# rtc.net
KiCad netlist of a schematic drawn in Altium Designer
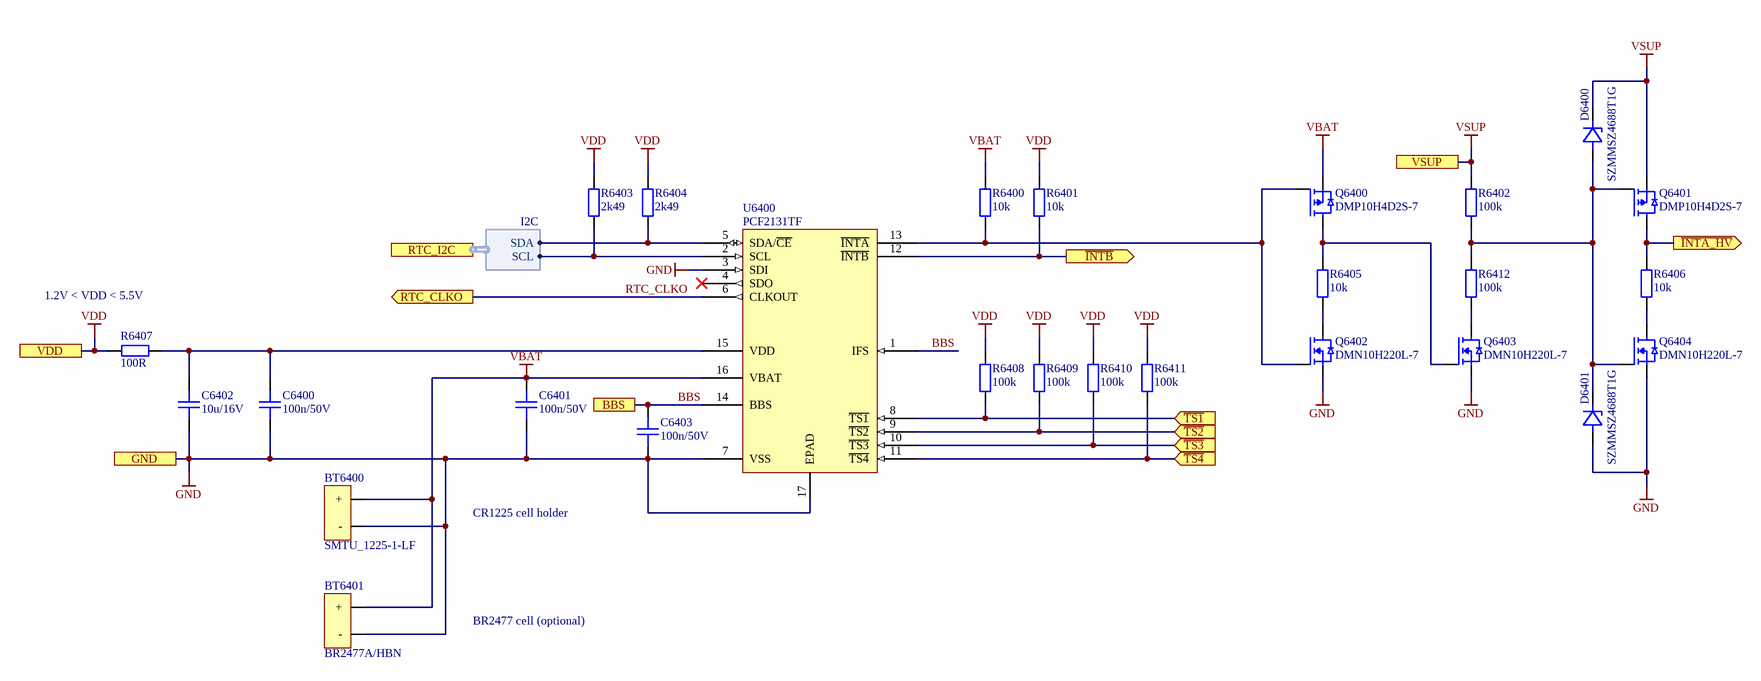
[diagram p0: rtc.SchDoc]

(export (version "E")
  (design (tool "Eeschema 10.0.6"))
  (components
    (comp (ref "BT6400")
      (value "SMTU_1225-1-LF")
      (footprint "SMTU_1225-1-LF")
      (description "SMTU 1225-1-LF, Battery Holder 1225")
      (fields (field (name "MANUFACTURER") "Renata"))
      (libsource (lib "OE750") (part "battery"))
    )
    (comp (ref "BT6401")
      (value "BR2477A/HBN")
      (footprint "BR2477A-HBN")
      (description "Coin Cell Battery 3V 1000mAH HI TEMP")
      (fields (field (name "MANUFACTURER") "Panasonic"))
      (libsource (lib "OE750") (part "battery"))
    )
    (comp (ref "C6400")
      (value "100n/50V")
      (footprint "CAPC1005X06N")
      (description "MLCC")
      (fields (field (name "PART NUMBER") "gen_C_ceramic_100n_50V_X7R_0402"))
      (libsource (lib "OE750") (part "C"))
    )
    (comp (ref "C6401")
      (value "100n/50V")
      (footprint "CAPC1005X06N")
      (description "MLCC")
      (fields (field (name "PART NUMBER") "gen_C_ceramic_100n_50V_X7R_0402"))
      (libsource (lib "OE750") (part "C"))
    )
    (comp (ref "C6402")
      (value "10u/16V")
      (footprint "CAPC2012X14N")
      (description "MLCC")
      (fields (field (name "PART NUMBER") "gen_C_ceramic_10u_16V_X7R_0805"))
      (libsource (lib "OE750") (part "C"))
    )
    (comp (ref "C6403")
      (value "100n/50V")
      (footprint "CAPC1005X06N")
      (description "MLCC")
      (fields (field (name "PART NUMBER") "gen_C_ceramic_100n_50V_X7R_0402"))
      (libsource (lib "OE750") (part "C"))
    )
    (comp (ref "D6400")
      (value "SZMMSZ4688T1G")
      (footprint "SOD-123_CASE-425-04-ISSUE-G")
      (description "Zener Diode")
      (fields (field (name "MANUFACTURER") "ON Semiconductor"))
      (libsource (lib "OE750") (part "D_Zener"))
    )
    (comp (ref "D6401")
      (value "SZMMSZ4688T1G")
      (footprint "SOD-123_CASE-425-04-ISSUE-G")
      (description "Zener Diode")
      (fields (field (name "MANUFACTURER") "ON Semiconductor"))
      (libsource (lib "OE750") (part "D_Zener"))
    )
    (comp (ref "Q6400")
      (value "DMP10H4D2S-7")
      (footprint "SOT95P237X110-3N")
      (description "MOSFET-Transistor, p-Kanal, 0.27 A, 100 V, 4.2 ohm")
      (fields (field (name "MANUFACTURER") "Diodes"))
      (libsource (lib "OE750") (part "PMOS"))
    )
    (comp (ref "Q6401")
      (value "DMP10H4D2S-7")
      (footprint "SOT95P237X110-3N")
      (description "MOSFET-Transistor, p-Kanal, 0.27 A, 100 V, 4.2 ohm")
      (fields (field (name "MANUFACTURER") "Diodes"))
      (libsource (lib "OE750") (part "PMOS"))
    )
    (comp (ref "Q6402")
      (value "DMN10H220L-7")
      (footprint "SOT95P237X110-3N")
      (description "MOSFET-Transistor, n-Kanal, 1.6 A, 100 V, 0.250 ohm")
      (fields (field (name "MANUFACTURER") "Diodes"))
      (libsource (lib "OE750") (part "NMOS"))
    )
    (comp (ref "Q6403")
      (value "DMN10H220L-7")
      (footprint "SOT95P237X110-3N")
      (description "MOSFET-Transistor, n-Kanal, 1.6 A, 100 V, 0.250 ohm")
      (fields (field (name "MANUFACTURER") "Diodes"))
      (libsource (lib "OE750") (part "NMOS"))
    )
    (comp (ref "Q6404")
      (value "DMN10H220L-7")
      (footprint "SOT95P237X110-3N")
      (description "MOSFET-Transistor, n-Kanal, 1.6 A, 100 V, 0.250 ohm")
      (fields (field (name "MANUFACTURER") "Diodes"))
      (libsource (lib "OE750") (part "NMOS"))
    )
    (comp (ref "R6400")
      (value "10k")
      (footprint "RESC1005X04N")
      (description "SMD Resistor 10k 0402")
      (fields (field (name "PART NUMBER") "gen_R_10k_0402") (field (name "TOLERANCE") "1%"))
      (libsource (lib "OE750") (part "R"))
    )
    (comp (ref "R6401")
      (value "10k")
      (footprint "RESC1005X04N")
      (description "SMD Resistor 10k 0402")
      (fields (field (name "PART NUMBER") "gen_R_10k_0402") (field (name "TOLERANCE") "1%"))
      (libsource (lib "OE750") (part "R"))
    )
    (comp (ref "R6402")
      (value "100k")
      (footprint "RESC1005X04N")
      (description "SMD Resistor 100k 0402")
      (fields (field (name "PART NUMBER") "gen_R_100k_0402") (field (name "TOLERANCE") "1%"))
      (libsource (lib "OE750") (part "R"))
    )
    (comp (ref "R6403")
      (value "2k49")
      (footprint "RESC1005X04N")
      (description "SMD Resistor 2k49 0402")
      (fields (field (name "PART NUMBER") "gen_R_2k49_0402") (field (name "TOLERANCE") "1%"))
      (libsource (lib "OE750") (part "R"))
    )
    (comp (ref "R6404")
      (value "2k49")
      (footprint "RESC1005X04N")
      (description "SMD Resistor 2k49 0402")
      (fields (field (name "PART NUMBER") "gen_R_2k49_0402") (field (name "TOLERANCE") "1%"))
      (libsource (lib "OE750") (part "R"))
    )
    (comp (ref "R6405")
      (value "10k")
      (footprint "RESC1005X04N")
      (description "SMD Resistor 10k 0402")
      (fields (field (name "PART NUMBER") "gen_R_10k_0402") (field (name "TOLERANCE") "1%"))
      (libsource (lib "OE750") (part "R"))
    )
    (comp (ref "R6406")
      (value "10k")
      (footprint "RESC1005X04N")
      (description "SMD Resistor 10k 0402")
      (fields (field (name "PART NUMBER") "gen_R_10k_0402") (field (name "TOLERANCE") "1%"))
      (libsource (lib "OE750") (part "R"))
    )
    (comp (ref "R6407")
      (value "100R")
      (footprint "RESC1005X04N")
      (description "SMD Resistor 100R 0402")
      (fields (field (name "PART NUMBER") "gen_R_100R_0402") (field (name "TOLERANCE") "1%"))
      (libsource (lib "OE750") (part "R"))
    )
    (comp (ref "R6408")
      (value "100k")
      (footprint "RESC1005X04N")
      (description "SMD Resistor 100k 0402")
      (fields (field (name "PART NUMBER") "gen_R_100k_0402") (field (name "TOLERANCE") "1%"))
      (libsource (lib "OE750") (part "R"))
    )
    (comp (ref "R6409")
      (value "100k")
      (footprint "RESC1005X04N")
      (description "SMD Resistor 100k 0402")
      (fields (field (name "PART NUMBER") "gen_R_100k_0402") (field (name "TOLERANCE") "1%"))
      (libsource (lib "OE750") (part "R"))
    )
    (comp (ref "R6410")
      (value "100k")
      (footprint "RESC1005X04N")
      (description "SMD Resistor 100k 0402")
      (fields (field (name "PART NUMBER") "gen_R_100k_0402") (field (name "TOLERANCE") "1%"))
      (libsource (lib "OE750") (part "R"))
    )
    (comp (ref "R6411")
      (value "100k")
      (footprint "RESC1005X04N")
      (description "SMD Resistor 100k 0402")
      (fields (field (name "PART NUMBER") "gen_R_100k_0402") (field (name "TOLERANCE") "1%"))
      (libsource (lib "OE750") (part "R"))
    )
    (comp (ref "R6412")
      (value "100k")
      (footprint "RESC1005X04N")
      (description "SMD Resistor 100k 0402")
      (fields (field (name "PART NUMBER") "gen_R_100k_0402") (field (name "TOLERANCE") "1%"))
      (libsource (lib "OE750") (part "R"))
    )
    (comp (ref "U6400")
      (value "PCF2131TF")
      (footprint "NXP_SOT1992-1")
      (description "Ultra low power and high accurate RTC with integrated quartz crystal")
      (fields (field (name "MANUFACTURER") "NXP"))
      (libsource (lib "OE750") (part "PCF2131"))
    )
  )
  (nets
    (net (code "2") (name "/BBS") (class "Default")
      (node (ref "C6403") (pin "2") (pinfunction "2_2") (pintype "passive"))
      (node (ref "U6400") (pin "1") (pinfunction "IFS_1") (pintype "input"))
      (node (ref "U6400") (pin "14") (pinfunction "BBS_14") (pintype "power_in"))
    )
    (net (code "3") (name "/INTA_HV") (class "Default")
      (node (ref "Q6401") (pin "D") (pinfunction "D_D") (pintype "passive"))
      (node (ref "R6406") (pin "2") (pinfunction "2_2") (pintype "passive"))
    )
    (net (code "4") (name "/INTB") (class "Default")
      (node (ref "R6401") (pin "1") (pinfunction "1_1") (pintype "passive"))
      (node (ref "U6400") (pin "12") (pinfunction "INTB_12") (pintype "open_collector"))
    )
    (net (code "5") (name "/RTC_CLKO") (class "Default")
      (node (ref "U6400") (pin "6") (pinfunction "CLKOUT_6") (pintype "output"))
    )
    (net (code "6") (name "/TS1") (class "Default")
      (node (ref "R6408") (pin "1") (pinfunction "1_1") (pintype "passive"))
      (node (ref "U6400") (pin "8") (pinfunction "TS1_8") (pintype "input"))
    )
    (net (code "7") (name "/TS2") (class "Default")
      (node (ref "R6409") (pin "1") (pinfunction "1_1") (pintype "passive"))
      (node (ref "U6400") (pin "9") (pinfunction "TS2_9") (pintype "input"))
    )
    (net (code "8") (name "/TS3") (class "Default")
      (node (ref "R6410") (pin "1") (pinfunction "1_1") (pintype "passive"))
      (node (ref "U6400") (pin "10") (pinfunction "TS3_10") (pintype "input"))
    )
    (net (code "9") (name "/TS4") (class "Default")
      (node (ref "R6411") (pin "1") (pinfunction "1_1") (pintype "passive"))
      (node (ref "U6400") (pin "11") (pinfunction "TS4_11") (pintype "input"))
    )
    (net (code "11") (name "GND") (class "Default")
      (node (ref "BT6400") (pin "-") (pinfunction "-_-") (pintype "power_in"))
      (node (ref "BT6401") (pin "-") (pinfunction "-_-") (pintype "power_in"))
      (node (ref "C6400") (pin "1") (pinfunction "1_1") (pintype "passive"))
      (node (ref "C6401") (pin "1") (pinfunction "1_1") (pintype "passive"))
      (node (ref "C6402") (pin "1") (pinfunction "1_1") (pintype "passive"))
      (node (ref "C6403") (pin "1") (pinfunction "1_1") (pintype "passive"))
      (node (ref "D6401") (pin "2") (pinfunction "A_2") (pintype "passive"))
      (node (ref "Q6402") (pin "S") (pinfunction "S_S") (pintype "passive"))
      (node (ref "Q6403") (pin "S") (pinfunction "S_S") (pintype "passive"))
      (node (ref "Q6404") (pin "S") (pinfunction "S_S") (pintype "passive"))
      (node (ref "U6400") (pin "17") (pinfunction "EPAD_17") (pintype "power_in"))
      (node (ref "U6400") (pin "3") (pinfunction "SDI_3") (pintype "input"))
      (node (ref "U6400") (pin "7") (pinfunction "VSS_7") (pintype "power_in"))
    )
    (net (code "12") (name "Net-(D6400-A)") (class "Default")
      (node (ref "D6400") (pin "2") (pinfunction "A_2") (pintype "passive"))
      (node (ref "D6401") (pin "1") (pinfunction "K_1") (pintype "passive"))
      (node (ref "Q6401") (pin "G") (pinfunction "G_G") (pintype "passive"))
      (node (ref "Q6404") (pin "G") (pinfunction "G_G") (pintype "passive"))
      (node (ref "R6402") (pin "1") (pinfunction "1_1") (pintype "passive"))
      (node (ref "R6412") (pin "2") (pinfunction "2_2") (pintype "passive"))
    )
    (net (code "13") (name "Net-(Q6400-PadD)") (class "Default")
      (node (ref "Q6400") (pin "D") (pinfunction "D_D") (pintype "passive"))
      (node (ref "Q6403") (pin "G") (pinfunction "G_G") (pintype "passive"))
      (node (ref "R6405") (pin "2") (pinfunction "2_2") (pintype "passive"))
    )
    (net (code "14") (name "Net-(Q6402-PadD)") (class "Default")
      (node (ref "Q6402") (pin "D") (pinfunction "D_D") (pintype "passive"))
      (node (ref "R6405") (pin "1") (pinfunction "1_1") (pintype "passive"))
    )
    (net (code "15") (name "Net-(Q6403-PadD)") (class "Default")
      (node (ref "Q6403") (pin "D") (pinfunction "D_D") (pintype "passive"))
      (node (ref "R6412") (pin "1") (pinfunction "1_1") (pintype "passive"))
    )
    (net (code "16") (name "Net-(Q6404-PadD)") (class "Default")
      (node (ref "Q6404") (pin "D") (pinfunction "D_D") (pintype "passive"))
      (node (ref "R6406") (pin "1") (pinfunction "1_1") (pintype "passive"))
    )
    (net (code "17") (name "Net-(U6400-INTA)") (class "Default")
      (node (ref "Q6400") (pin "G") (pinfunction "G_G") (pintype "passive"))
      (node (ref "Q6402") (pin "G") (pinfunction "G_G") (pintype "passive"))
      (node (ref "R6400") (pin "1") (pinfunction "1_1") (pintype "passive"))
      (node (ref "U6400") (pin "13") (pinfunction "INTA_13") (pintype "open_collector"))
    )
    (net (code "18") (name "Net-(U6400-SCL)") (class "Default")
      (node (ref "R6403") (pin "1") (pinfunction "1_1") (pintype "passive"))
      (node (ref "U6400") (pin "2") (pinfunction "SCL_2") (pintype "input"))
    )
    (net (code "19") (name "Net-(U6400-SDA{slash}~{CE})") (class "Default")
      (node (ref "R6404") (pin "1") (pinfunction "1_1") (pintype "passive"))
      (node (ref "U6400") (pin "5") (pinfunction "SDA/~{CE}_5") (pintype "bidirectional"))
    )
    (net (code "20") (name "Net-(U6400-VDD)") (class "Default")
      (node (ref "C6400") (pin "2") (pinfunction "2_2") (pintype "passive"))
      (node (ref "C6402") (pin "2") (pinfunction "2_2") (pintype "passive"))
      (node (ref "R6407") (pin "1") (pinfunction "1_1") (pintype "passive"))
      (node (ref "U6400") (pin "15") (pinfunction "VDD_15") (pintype "power_in"))
    )
    (net (code "21") (name "VBAT") (class "Default")
      (node (ref "BT6400") (pin "+") (pinfunction "+_+") (pintype "power_in"))
      (node (ref "BT6401") (pin "+") (pinfunction "+_+") (pintype "power_in"))
      (node (ref "C6401") (pin "2") (pinfunction "2_2") (pintype "passive"))
      (node (ref "Q6400") (pin "S") (pinfunction "S_S") (pintype "passive"))
      (node (ref "R6400") (pin "2") (pinfunction "2_2") (pintype "passive"))
      (node (ref "U6400") (pin "16") (pinfunction "VBAT_16") (pintype "power_in"))
    )
    (net (code "22") (name "VDD") (class "Default")
      (node (ref "R6401") (pin "2") (pinfunction "2_2") (pintype "passive"))
      (node (ref "R6403") (pin "2") (pinfunction "2_2") (pintype "passive"))
      (node (ref "R6404") (pin "2") (pinfunction "2_2") (pintype "passive"))
      (node (ref "R6407") (pin "2") (pinfunction "2_2") (pintype "passive"))
      (node (ref "R6408") (pin "2") (pinfunction "2_2") (pintype "passive"))
      (node (ref "R6409") (pin "2") (pinfunction "2_2") (pintype "passive"))
      (node (ref "R6410") (pin "2") (pinfunction "2_2") (pintype "passive"))
      (node (ref "R6411") (pin "2") (pinfunction "2_2") (pintype "passive"))
    )
    (net (code "23") (name "VSUP") (class "Default")
      (node (ref "D6400") (pin "1") (pinfunction "K_1") (pintype "passive"))
      (node (ref "Q6401") (pin "S") (pinfunction "S_S") (pintype "passive"))
      (node (ref "R6402") (pin "2") (pinfunction "2_2") (pintype "passive"))
    )
    (net (code "24") (name "unconnected-(U6400-SDO-Pad4)") (class "Default")
      (node (ref "U6400") (pin "4") (pinfunction "SDO_4") (pintype "output+no_connect"))
    )
  )
)
